# G888A.net
KiCad netlist of a schematic drawn in EAGLE
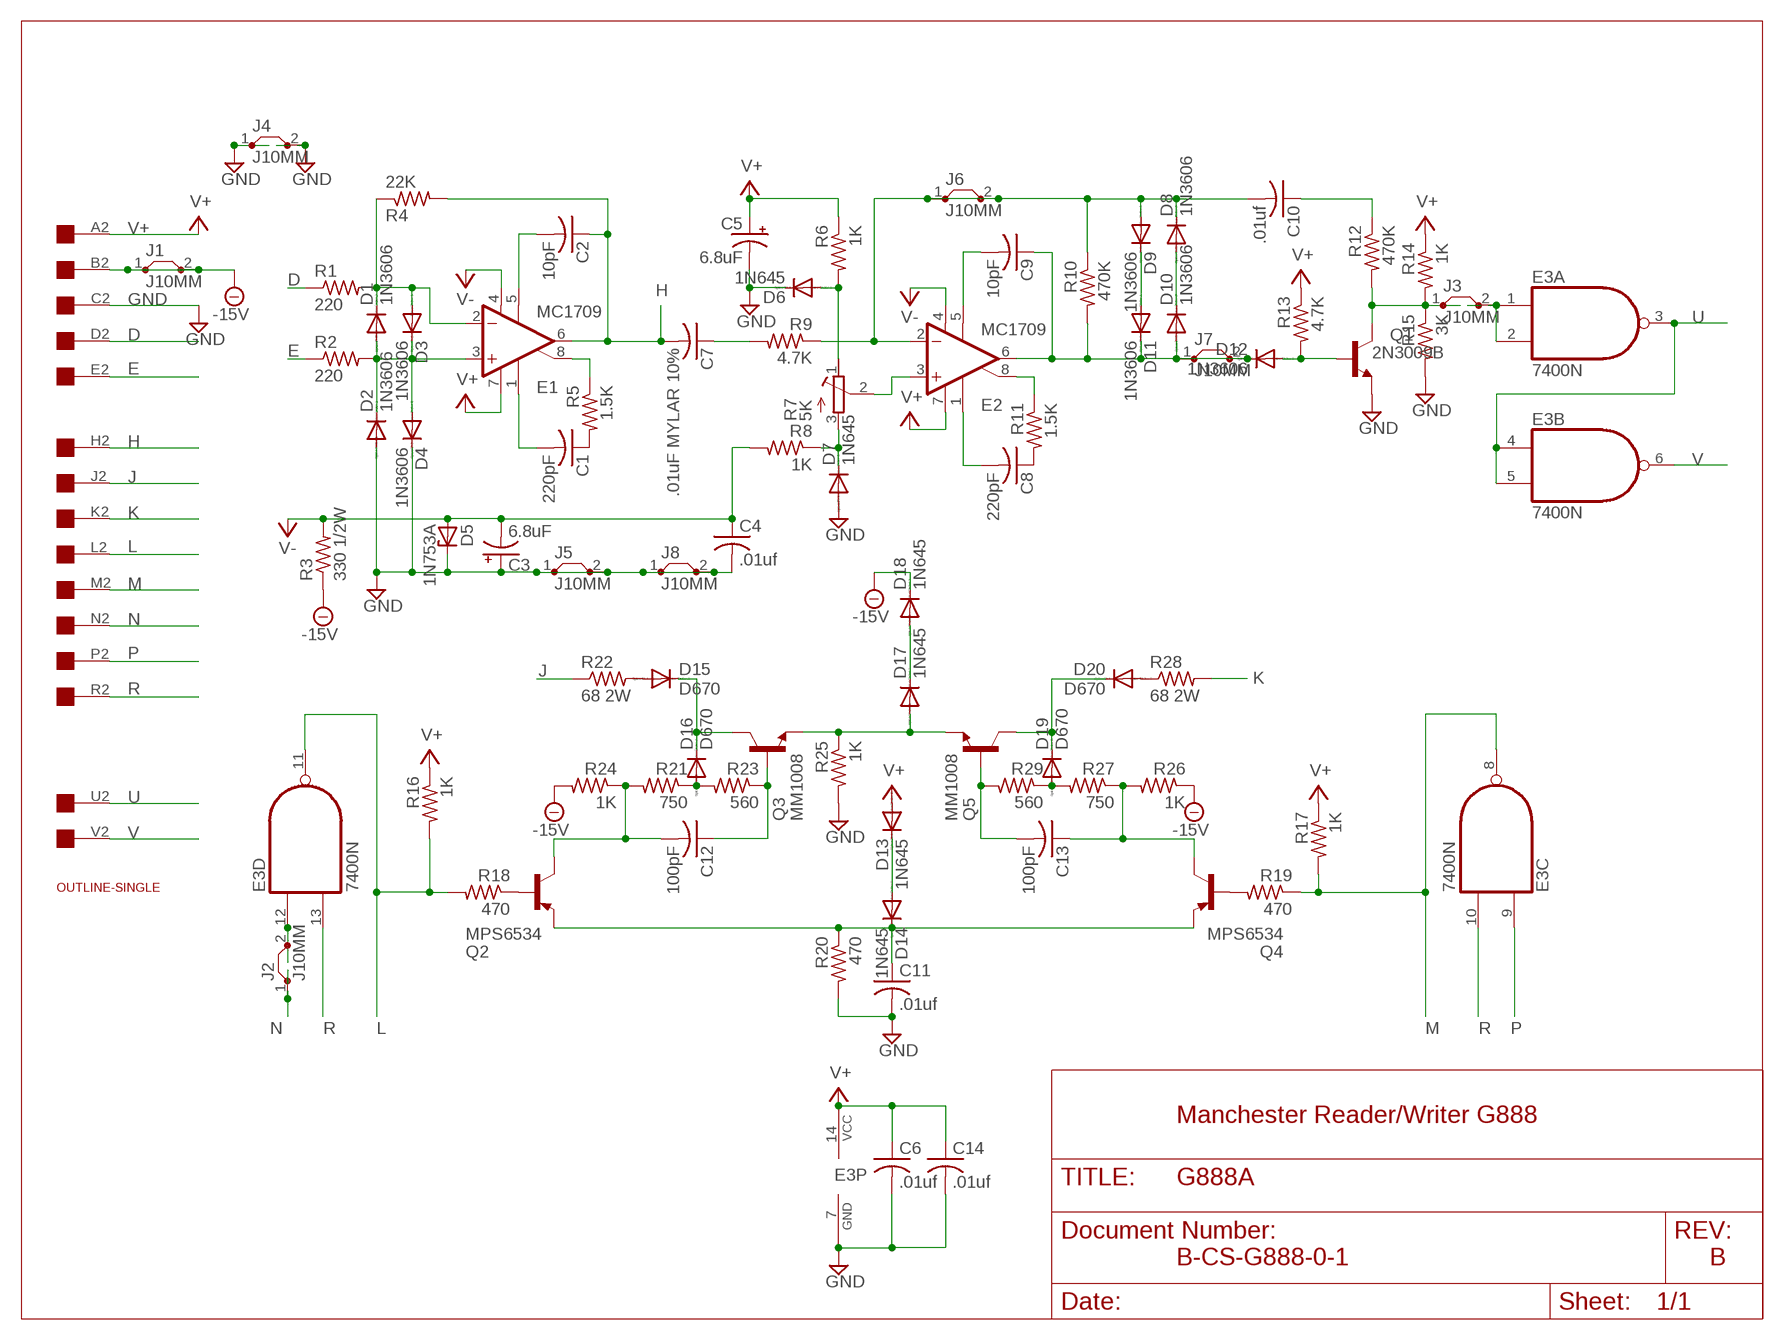
[diagram p0: schematic, sheet 1]

(export (version "E")
  (design (tool "Eeschema 10.0.6"))
  (components
    (comp (ref "C1")
      (value "220pF")
      (footprint "eagle-import:C050-025X075")
      (libsource (lib "eagle-import") (part "C-US050-025X075"))
    )
    (comp (ref "C2")
      (value "10pF")
      (footprint "eagle-import:C050-025X075")
      (libsource (lib "eagle-import") (part "C-US050-025X075"))
    )
    (comp (ref "C3")
      (value "6.8uF")
      (footprint "eagle-import:E12-8")
      (libsource (lib "eagle-import") (part "CPOL-USE20-8AXIAL"))
    )
    (comp (ref "C4")
      (value ".01uf")
      (footprint "eagle-import:C050-025X075")
      (libsource (lib "eagle-import") (part "C-US050-025X075"))
    )
    (comp (ref "C5")
      (value "6.8uF")
      (footprint "eagle-import:E12-8")
      (libsource (lib "eagle-import") (part "CPOL-USE20-8AXIAL"))
    )
    (comp (ref "C6")
      (value ".01uf")
      (footprint "eagle-import:C050-025X075")
      (libsource (lib "eagle-import") (part "C-US050-025X075"))
    )
    (comp (ref "C7")
      (value ".01uF MYLAR 10%")
      (footprint "eagle-import:C225-062X268")
      (libsource (lib "eagle-import") (part "C-US225-062X268"))
    )
    (comp (ref "C8")
      (value "220pF")
      (footprint "eagle-import:C050-025X075")
      (libsource (lib "eagle-import") (part "C-US050-025X075"))
    )
    (comp (ref "C9")
      (value "10pF")
      (footprint "eagle-import:C050-025X075")
      (libsource (lib "eagle-import") (part "C-US050-025X075"))
    )
    (comp (ref "C10")
      (value ".01uf")
      (footprint "eagle-import:C050-025X075")
      (libsource (lib "eagle-import") (part "C-US050-025X075"))
    )
    (comp (ref "C11")
      (value ".01uf")
      (footprint "eagle-import:C050-025X075")
      (libsource (lib "eagle-import") (part "C-US050-025X075"))
    )
    (comp (ref "C12")
      (value "100pF")
      (footprint "eagle-import:C050-025X075")
      (libsource (lib "eagle-import") (part "C-US050-025X075"))
    )
    (comp (ref "C13")
      (value "100pF")
      (footprint "eagle-import:C050-025X075")
      (libsource (lib "eagle-import") (part "C-US050-025X075"))
    )
    (comp (ref "C14")
      (value ".01uf")
      (footprint "eagle-import:C050-025X075")
      (libsource (lib "eagle-import") (part "C-US050-025X075"))
    )
    (comp (ref "D1")
      (value "1N3606")
      (footprint "eagle-import:DO35-10")
      (libsource (lib "eagle-import") (part "DIODE-DO35-10"))
    )
    (comp (ref "D2")
      (value "1N3606")
      (footprint "eagle-import:DO35-10")
      (libsource (lib "eagle-import") (part "DIODE-DO35-10"))
    )
    (comp (ref "D3")
      (value "1N3606")
      (footprint "eagle-import:DO35-10")
      (libsource (lib "eagle-import") (part "DIODE-DO35-10"))
    )
    (comp (ref "D4")
      (value "1N3606")
      (footprint "eagle-import:DO35-10")
      (libsource (lib "eagle-import") (part "DIODE-DO35-10"))
    )
    (comp (ref "D5")
      (value "1N753A")
      (footprint "eagle-import:DO35Z10")
      (libsource (lib "eagle-import") (part "ZENER-DIODEDO35Z10"))
    )
    (comp (ref "D6")
      (value "1N645")
      (footprint "eagle-import:DO35-10")
      (libsource (lib "eagle-import") (part "DIODE-DO35-10"))
    )
    (comp (ref "D7")
      (value "1N645")
      (footprint "eagle-import:DO35-10")
      (libsource (lib "eagle-import") (part "DIODE-DO35-10"))
    )
    (comp (ref "D8")
      (value "1N3606")
      (footprint "eagle-import:DO35-10")
      (libsource (lib "eagle-import") (part "DIODE-DO35-10"))
    )
    (comp (ref "D9")
      (value "1N3606")
      (footprint "eagle-import:DO35-10")
      (libsource (lib "eagle-import") (part "DIODE-DO35-10"))
    )
    (comp (ref "D10")
      (value "1N3606")
      (footprint "eagle-import:DO35-10")
      (libsource (lib "eagle-import") (part "DIODE-DO35-10"))
    )
    (comp (ref "D11")
      (value "1N3606")
      (footprint "eagle-import:DO35-10")
      (libsource (lib "eagle-import") (part "DIODE-DO35-10"))
    )
    (comp (ref "D12")
      (value "1N3606")
      (footprint "eagle-import:DO35-10")
      (libsource (lib "eagle-import") (part "DIODE-DO35-10"))
    )
    (comp (ref "D13")
      (value "1N645")
      (footprint "eagle-import:DO35-10")
      (libsource (lib "eagle-import") (part "DIODE-DO35-10"))
    )
    (comp (ref "D14")
      (value "1N645")
      (footprint "eagle-import:DO35-10")
      (libsource (lib "eagle-import") (part "DIODE-DO35-10"))
    )
    (comp (ref "D15")
      (value "D670")
      (footprint "eagle-import:DO35-10")
      (libsource (lib "eagle-import") (part "DIODE-DO35-10"))
    )
    (comp (ref "D16")
      (value "D670")
      (footprint "eagle-import:DO35-10")
      (libsource (lib "eagle-import") (part "DIODE-DO35-10"))
    )
    (comp (ref "D17")
      (value "1N645")
      (footprint "eagle-import:DO35-10")
      (libsource (lib "eagle-import") (part "DIODE-DO35-10"))
    )
    (comp (ref "D18")
      (value "1N645")
      (footprint "eagle-import:DO35-10")
      (libsource (lib "eagle-import") (part "DIODE-DO35-10"))
    )
    (comp (ref "D19")
      (value "D670")
      (footprint "eagle-import:DO35-10")
      (libsource (lib "eagle-import") (part "DIODE-DO35-10"))
    )
    (comp (ref "D20")
      (value "D670")
      (footprint "eagle-import:DO35-10")
      (libsource (lib "eagle-import") (part "DIODE-DO35-10"))
    )
    (comp (ref "E1")
      (value "MC1709")
      (footprint "eagle-import:H08C")
      (libsource (lib "eagle-import") (part "MC1709"))
    )
    (comp (ref "E2")
      (value "MC1709")
      (footprint "eagle-import:H08C")
      (libsource (lib "eagle-import") (part "MC1709"))
    )
    (comp (ref "E3")
      (value "7400N")
      (footprint "eagle-import:DIL14")
      (libsource (lib "eagle-import") (part "7400N"))
    )
    (comp (ref "J1")
      (value "J10MM")
      (footprint "eagle-import:10")
      (libsource (lib "eagle-import") (part "J10MM"))
    )
    (comp (ref "J2")
      (value "J10MM")
      (footprint "eagle-import:10")
      (libsource (lib "eagle-import") (part "J10MM"))
    )
    (comp (ref "J3")
      (value "J10MM")
      (footprint "eagle-import:10")
      (libsource (lib "eagle-import") (part "J10MM"))
    )
    (comp (ref "J4")
      (value "J10MM")
      (footprint "eagle-import:10")
      (libsource (lib "eagle-import") (part "J10MM"))
    )
    (comp (ref "J5")
      (value "J10MM")
      (footprint "eagle-import:10")
      (libsource (lib "eagle-import") (part "J10MM"))
    )
    (comp (ref "J6")
      (value "J10MM")
      (footprint "eagle-import:10")
      (libsource (lib "eagle-import") (part "J10MM"))
    )
    (comp (ref "J7")
      (value "J10MM")
      (footprint "eagle-import:10")
      (libsource (lib "eagle-import") (part "J10MM"))
    )
    (comp (ref "J8")
      (value "J10MM")
      (footprint "eagle-import:10")
      (libsource (lib "eagle-import") (part "J10MM"))
    )
    (comp (ref "Q1")
      (value "2N3009B")
      (footprint "eagle-import:TO39")
      (libsource (lib "eagle-import") (part "2N1711"))
    )
    (comp (ref "Q2")
      (value "MPS6534")
      (footprint "eagle-import:TO39")
      (libsource (lib "eagle-import") (part "2N5415"))
    )
    (comp (ref "Q3")
      (value "MM1008")
      (footprint "eagle-import:TO39")
      (libsource (lib "eagle-import") (part "2N1711"))
    )
    (comp (ref "Q4")
      (value "MPS6534")
      (footprint "eagle-import:TO39")
      (libsource (lib "eagle-import") (part "2N5415"))
    )
    (comp (ref "Q5")
      (value "MM1008")
      (footprint "eagle-import:TO39")
      (libsource (lib "eagle-import") (part "2N1711"))
    )
    (comp (ref "R1")
      (value "220")
      (footprint "eagle-import:0207_10")
      (libsource (lib "eagle-import") (part "R-US_0207/10"))
    )
    (comp (ref "R2")
      (value "220")
      (footprint "eagle-import:0207_10")
      (libsource (lib "eagle-import") (part "R-US_0207/10"))
    )
    (comp (ref "R3")
      (value "330 1/2W")
      (footprint "eagle-import:0411_15")
      (libsource (lib "eagle-import") (part "R-US_0411/15"))
    )
    (comp (ref "R4")
      (value "22K")
      (footprint "eagle-import:0207_10")
      (libsource (lib "eagle-import") (part "R-US_0207/10"))
    )
    (comp (ref "R5")
      (value "1.5K")
      (footprint "eagle-import:0207_10")
      (libsource (lib "eagle-import") (part "R-US_0207/10"))
    )
    (comp (ref "R6")
      (value "1K")
      (footprint "eagle-import:0207_10")
      (libsource (lib "eagle-import") (part "R-US_0207/10"))
    )
    (comp (ref "R7")
      (value "5K")
      (footprint "eagle-import:3006Y")
      (libsource (lib "eagle-import") (part "275P"))
    )
    (comp (ref "R8")
      (value "1K")
      (footprint "eagle-import:0207_10")
      (libsource (lib "eagle-import") (part "R-US_0207/10"))
    )
    (comp (ref "R9")
      (value "4.7K")
      (footprint "eagle-import:0207_10")
      (libsource (lib "eagle-import") (part "R-US_0207/10"))
    )
    (comp (ref "R10")
      (value "470K")
      (footprint "eagle-import:0207_10")
      (libsource (lib "eagle-import") (part "R-US_0207/10"))
    )
    (comp (ref "R11")
      (value "1.5K")
      (footprint "eagle-import:0207_10")
      (libsource (lib "eagle-import") (part "R-US_0207/10"))
    )
    (comp (ref "R12")
      (value "470K")
      (footprint "eagle-import:0207_10")
      (libsource (lib "eagle-import") (part "R-US_0207/10"))
    )
    (comp (ref "R13")
      (value "4.7K")
      (footprint "eagle-import:0207_10")
      (libsource (lib "eagle-import") (part "R-US_0207/10"))
    )
    (comp (ref "R14")
      (value "1K")
      (footprint "eagle-import:0207_10")
      (libsource (lib "eagle-import") (part "R-US_0207/10"))
    )
    (comp (ref "R15")
      (value "3K")
      (footprint "eagle-import:0207_10")
      (libsource (lib "eagle-import") (part "R-US_0207/10"))
    )
    (comp (ref "R16")
      (value "1K")
      (footprint "eagle-import:0207_10")
      (libsource (lib "eagle-import") (part "R-US_0207/10"))
    )
    (comp (ref "R17")
      (value "1K")
      (footprint "eagle-import:0207_10")
      (libsource (lib "eagle-import") (part "R-US_0207/10"))
    )
    (comp (ref "R18")
      (value "470")
      (footprint "eagle-import:0207_10")
      (libsource (lib "eagle-import") (part "R-US_0207/10"))
    )
    (comp (ref "R19")
      (value "470")
      (footprint "eagle-import:0207_10")
      (libsource (lib "eagle-import") (part "R-US_0207/10"))
    )
    (comp (ref "R20")
      (value "470")
      (footprint "eagle-import:0207_10")
      (libsource (lib "eagle-import") (part "R-US_0207/10"))
    )
    (comp (ref "R21")
      (value "750")
      (footprint "eagle-import:0207_10")
      (libsource (lib "eagle-import") (part "R-US_0207/10"))
    )
    (comp (ref "R22")
      (value "68 2W")
      (footprint "eagle-import:P0817_22")
      (libsource (lib "eagle-import") (part "R-US_0817/22"))
    )
    (comp (ref "R23")
      (value "560")
      (footprint "eagle-import:0207_10")
      (libsource (lib "eagle-import") (part "R-US_0207/10"))
    )
    (comp (ref "R24")
      (value "1K")
      (footprint "eagle-import:0207_10")
      (libsource (lib "eagle-import") (part "R-US_0207/10"))
    )
    (comp (ref "R25")
      (value "1K")
      (footprint "eagle-import:0207_10")
      (libsource (lib "eagle-import") (part "R-US_0207/10"))
    )
    (comp (ref "R26")
      (value "1K")
      (footprint "eagle-import:0207_10")
      (libsource (lib "eagle-import") (part "R-US_0207/10"))
    )
    (comp (ref "R27")
      (value "750")
      (footprint "eagle-import:0207_10")
      (libsource (lib "eagle-import") (part "R-US_0207/10"))
    )
    (comp (ref "R28")
      (value "68 2W")
      (footprint "eagle-import:P0817_22")
      (libsource (lib "eagle-import") (part "R-US_0817/22"))
    )
    (comp (ref "R29")
      (value "560")
      (footprint "eagle-import:0207_10")
      (libsource (lib "eagle-import") (part "R-US_0207/10"))
    )
    (comp (ref "U$1")
      (value "EDGE-1")
      (footprint "eagle-import:EDGE-CON1")
      (libsource (lib "eagle-import") (part "EDGE-1"))
    )
    (comp (ref "U$4")
      (value "OUTLINE-SINGLE")
      (footprint "eagle-import:SINGLE")
      (libsource (lib "eagle-import") (part "OUTLINE-SINGLE"))
    )
  )
  (nets
    (net (code "1") (name "-15V") (class "Default")
      (node (ref "D18") (pin "C") (pinfunction "C_C") (pintype "passive"))
      (node (ref "J1") (pin "1") (pinfunction "1_1") (pintype "passive"))
      (node (ref "J1") (pin "2") (pinfunction "2_2") (pintype "passive"))
      (node (ref "R24") (pin "2") (pinfunction "2_2") (pintype "passive"))
      (node (ref "R26") (pin "1") (pinfunction "1_1") (pintype "passive"))
      (node (ref "R3") (pin "1") (pinfunction "1_1") (pintype "passive"))
      (node (ref "U$1") (pin "B2") (pinfunction "1_B2") (pintype "bidirectional"))
    )
    (net (code "2") (name "/D") (class "Default")
      (node (ref "R1") (pin "1") (pinfunction "1_1") (pintype "passive"))
      (node (ref "U$1") (pin "D2") (pinfunction "1_D2") (pintype "bidirectional"))
    )
    (net (code "3") (name "/E") (class "Default")
      (node (ref "R2") (pin "1") (pinfunction "1_1") (pintype "passive"))
      (node (ref "U$1") (pin "E2") (pinfunction "1_E2") (pintype "bidirectional"))
    )
    (net (code "4") (name "/H") (class "Default")
      (node (ref "C2") (pin "1") (pinfunction "1_1") (pintype "passive"))
      (node (ref "C7") (pin "2") (pinfunction "2_2") (pintype "passive"))
      (node (ref "E1") (pin "6") (pinfunction "OUT_6") (pintype "output"))
      (node (ref "R4") (pin "2") (pinfunction "2_2") (pintype "passive"))
      (node (ref "U$1") (pin "H2") (pinfunction "1_H2") (pintype "bidirectional"))
    )
    (net (code "5") (name "/J") (class "Default")
      (node (ref "R22") (pin "1") (pinfunction "1_1") (pintype "passive"))
      (node (ref "U$1") (pin "J2") (pinfunction "1_J2") (pintype "bidirectional"))
    )
    (net (code "6") (name "/K") (class "Default")
      (node (ref "R28") (pin "2") (pinfunction "2_2") (pintype "passive"))
      (node (ref "U$1") (pin "K2") (pinfunction "1_K2") (pintype "bidirectional"))
    )
    (net (code "7") (name "/L") (class "Default")
      (node (ref "E3") (pin "11") (pinfunction "O_11") (pintype "output"))
      (node (ref "R16") (pin "2") (pinfunction "2_2") (pintype "passive"))
      (node (ref "R18") (pin "2") (pinfunction "2_2") (pintype "passive"))
      (node (ref "U$1") (pin "L2") (pinfunction "1_L2") (pintype "bidirectional"))
    )
    (net (code "8") (name "/M") (class "Default")
      (node (ref "E3") (pin "8") (pinfunction "O_8") (pintype "output"))
      (node (ref "R17") (pin "2") (pinfunction "2_2") (pintype "passive"))
      (node (ref "R19") (pin "1") (pinfunction "1_1") (pintype "passive"))
      (node (ref "U$1") (pin "M2") (pinfunction "1_M2") (pintype "bidirectional"))
    )
    (net (code "9") (name "/N") (class "Default")
      (node (ref "E3") (pin "12") (pinfunction "I0_12") (pintype "input"))
      (node (ref "J2") (pin "1") (pinfunction "1_1") (pintype "passive"))
      (node (ref "J2") (pin "2") (pinfunction "2_2") (pintype "passive"))
      (node (ref "U$1") (pin "N2") (pinfunction "1_N2") (pintype "bidirectional"))
    )
    (net (code "10") (name "/P") (class "Default")
      (node (ref "E3") (pin "9") (pinfunction "I0_9") (pintype "input"))
      (node (ref "U$1") (pin "P2") (pinfunction "1_P2") (pintype "bidirectional"))
    )
    (net (code "11") (name "/R") (class "Default")
      (node (ref "E3") (pin "10") (pinfunction "I1_10") (pintype "input"))
      (node (ref "E3") (pin "13") (pinfunction "I1_13") (pintype "input"))
      (node (ref "U$1") (pin "R2") (pinfunction "1_R2") (pintype "bidirectional"))
    )
    (net (code "12") (name "/U") (class "Default")
      (node (ref "E3") (pin "3") (pinfunction "O_3") (pintype "output"))
      (node (ref "E3") (pin "4") (pinfunction "I0_4") (pintype "input"))
      (node (ref "E3") (pin "5") (pinfunction "I1_5") (pintype "input"))
      (node (ref "U$1") (pin "U2") (pinfunction "1_U2") (pintype "bidirectional"))
    )
    (net (code "13") (name "/V") (class "Default")
      (node (ref "E3") (pin "6") (pinfunction "O_6") (pintype "output"))
      (node (ref "U$1") (pin "V2") (pinfunction "1_V2") (pintype "bidirectional"))
    )
    (net (code "14") (name "GND") (class "Default")
      (node (ref "C11") (pin "2") (pinfunction "2_2") (pintype "passive"))
      (node (ref "C14") (pin "2") (pinfunction "2_2") (pintype "passive"))
      (node (ref "C3") (pin "+") (pinfunction "+_+") (pintype "passive"))
      (node (ref "C4") (pin "2") (pinfunction "2_2") (pintype "passive"))
      (node (ref "C5") (pin "-") (pinfunction "-_-") (pintype "passive"))
      (node (ref "C6") (pin "2") (pinfunction "2_2") (pintype "passive"))
      (node (ref "D2") (pin "A") (pinfunction "A_A") (pintype "passive"))
      (node (ref "D4") (pin "C") (pinfunction "C_C") (pintype "passive"))
      (node (ref "D5") (pin "C") (pinfunction "C_C") (pintype "passive"))
      (node (ref "D6") (pin "C") (pinfunction "C_C") (pintype "passive"))
      (node (ref "D7") (pin "A") (pinfunction "A_A") (pintype "passive"))
      (node (ref "E3") (pin "7") (pinfunction "GND_7") (pintype "power_in"))
      (node (ref "J4") (pin "1") (pinfunction "1_1") (pintype "passive"))
      (node (ref "J4") (pin "2") (pinfunction "2_2") (pintype "passive"))
      (node (ref "J5") (pin "1") (pinfunction "1_1") (pintype "passive"))
      (node (ref "J5") (pin "2") (pinfunction "2_2") (pintype "passive"))
      (node (ref "J8") (pin "1") (pinfunction "1_1") (pintype "passive"))
      (node (ref "J8") (pin "2") (pinfunction "2_2") (pintype "passive"))
      (node (ref "Q1") (pin "1") (pinfunction "E_1") (pintype "passive"))
      (node (ref "R15") (pin "2") (pinfunction "2_2") (pintype "passive"))
      (node (ref "R20") (pin "2") (pinfunction "2_2") (pintype "passive"))
      (node (ref "R25") (pin "2") (pinfunction "2_2") (pintype "passive"))
      (node (ref "U$1") (pin "C2") (pinfunction "1_C2") (pintype "bidirectional"))
    )
    (net (code "15") (name "Net-(C1-Pad1)") (class "Default")
      (node (ref "C1") (pin "1") (pinfunction "1_1") (pintype "passive"))
      (node (ref "R5") (pin "2") (pinfunction "2_2") (pintype "passive"))
    )
    (net (code "16") (name "Net-(C7-Pad1)") (class "Default")
      (node (ref "C7") (pin "1") (pinfunction "1_1") (pintype "passive"))
      (node (ref "R9") (pin "2") (pinfunction "2_2") (pintype "passive"))
    )
    (net (code "17") (name "Net-(C8-Pad1)") (class "Default")
      (node (ref "C8") (pin "1") (pinfunction "1_1") (pintype "passive"))
      (node (ref "R11") (pin "2") (pinfunction "2_2") (pintype "passive"))
    )
    (net (code "18") (name "Net-(C10-Pad1)") (class "Default")
      (node (ref "C10") (pin "1") (pinfunction "1_1") (pintype "passive"))
      (node (ref "R12") (pin "1") (pinfunction "1_1") (pintype "passive"))
    )
    (net (code "19") (name "Net-(D10-PadC)") (class "Default")
      (node (ref "D10") (pin "C") (pinfunction "C_C") (pintype "passive"))
      (node (ref "D8") (pin "A") (pinfunction "A_A") (pintype "passive"))
    )
    (net (code "20") (name "Net-(D11-PadA)") (class "Default")
      (node (ref "D11") (pin "A") (pinfunction "A_A") (pintype "passive"))
      (node (ref "D9") (pin "C") (pinfunction "C_C") (pintype "passive"))
    )
    (net (code "21") (name "Net-(D13-PadC)") (class "Default")
      (node (ref "D13") (pin "C") (pinfunction "C_C") (pintype "passive"))
      (node (ref "D14") (pin "A") (pinfunction "A_A") (pintype "passive"))
    )
    (net (code "22") (name "Net-(D15-PadA)") (class "Default")
      (node (ref "D15") (pin "A") (pinfunction "A_A") (pintype "passive"))
      (node (ref "R22") (pin "2") (pinfunction "2_2") (pintype "passive"))
    )
    (net (code "23") (name "Net-(D16-PadA)") (class "Default")
      (node (ref "D16") (pin "A") (pinfunction "A_A") (pintype "passive"))
      (node (ref "R21") (pin "1") (pinfunction "1_1") (pintype "passive"))
      (node (ref "R23") (pin "2") (pinfunction "2_2") (pintype "passive"))
    )
    (net (code "24") (name "Net-(D17-PadC)") (class "Default")
      (node (ref "D17") (pin "C") (pinfunction "C_C") (pintype "passive"))
      (node (ref "D18") (pin "A") (pinfunction "A_A") (pintype "passive"))
    )
    (net (code "25") (name "Net-(D19-PadA)") (class "Default")
      (node (ref "D19") (pin "A") (pinfunction "A_A") (pintype "passive"))
      (node (ref "R27") (pin "2") (pinfunction "2_2") (pintype "passive"))
      (node (ref "R29") (pin "1") (pinfunction "1_1") (pintype "passive"))
    )
    (net (code "26") (name "Net-(D20-PadA)") (class "Default")
      (node (ref "D20") (pin "A") (pinfunction "A_A") (pintype "passive"))
      (node (ref "R28") (pin "1") (pinfunction "1_1") (pintype "passive"))
    )
    (net (code "27") (name "Net-(E1-+IN)") (class "Default")
      (node (ref "D1") (pin "A") (pinfunction "A_A") (pintype "passive"))
      (node (ref "D2") (pin "C") (pinfunction "C_C") (pintype "passive"))
      (node (ref "D3") (pin "C") (pinfunction "C_C") (pintype "passive"))
      (node (ref "D4") (pin "A") (pinfunction "A_A") (pintype "passive"))
      (node (ref "E1") (pin "3") (pinfunction "+IN_3") (pintype "input"))
      (node (ref "R2") (pin "2") (pinfunction "2_2") (pintype "passive"))
    )
    (net (code "28") (name "Net-(E1--IN)") (class "Default")
      (node (ref "D1") (pin "C") (pinfunction "C_C") (pintype "passive"))
      (node (ref "D3") (pin "A") (pinfunction "A_A") (pintype "passive"))
      (node (ref "E1") (pin "2") (pinfunction "-IN_2") (pintype "input"))
      (node (ref "R1") (pin "2") (pinfunction "2_2") (pintype "passive"))
      (node (ref "R4") (pin "1") (pinfunction "1_1") (pintype "passive"))
    )
    (net (code "29") (name "Net-(E1-ON1)") (class "Default")
      (node (ref "C1") (pin "2") (pinfunction "2_2") (pintype "passive"))
      (node (ref "E1") (pin "1") (pinfunction "ON1_1") (pintype "passive"))
    )
    (net (code "30") (name "Net-(E1-ON2)") (class "Default")
      (node (ref "E1") (pin "8") (pinfunction "ON2_8") (pintype "passive"))
      (node (ref "R5") (pin "1") (pinfunction "1_1") (pintype "passive"))
    )
    (net (code "31") (name "Net-(E1-OPT)") (class "Default")
      (node (ref "C2") (pin "2") (pinfunction "2_2") (pintype "passive"))
      (node (ref "E1") (pin "5") (pinfunction "OPT_5") (pintype "passive"))
    )
    (net (code "32") (name "Net-(E2-+IN)") (class "Default")
      (node (ref "E2") (pin "3") (pinfunction "+IN_3") (pintype "input"))
      (node (ref "R7") (pin "2") (pinfunction "S_2") (pintype "passive"))
    )
    (net (code "33") (name "Net-(E2--IN)") (class "Default")
      (node (ref "C10") (pin "2") (pinfunction "2_2") (pintype "passive"))
      (node (ref "D8") (pin "C") (pinfunction "C_C") (pintype "passive"))
      (node (ref "D9") (pin "A") (pinfunction "A_A") (pintype "passive"))
      (node (ref "E2") (pin "2") (pinfunction "-IN_2") (pintype "input"))
      (node (ref "J6") (pin "1") (pinfunction "1_1") (pintype "passive"))
      (node (ref "J6") (pin "2") (pinfunction "2_2") (pintype "passive"))
      (node (ref "R10") (pin "1") (pinfunction "1_1") (pintype "passive"))
      (node (ref "R9") (pin "1") (pinfunction "1_1") (pintype "passive"))
    )
    (net (code "34") (name "Net-(E2-ON1)") (class "Default")
      (node (ref "C8") (pin "2") (pinfunction "2_2") (pintype "passive"))
      (node (ref "E2") (pin "1") (pinfunction "ON1_1") (pintype "passive"))
    )
    (net (code "35") (name "Net-(E2-ON2)") (class "Default")
      (node (ref "E2") (pin "8") (pinfunction "ON2_8") (pintype "passive"))
      (node (ref "R11") (pin "1") (pinfunction "1_1") (pintype "passive"))
    )
    (net (code "36") (name "Net-(E2-OPT)") (class "Default")
      (node (ref "C9") (pin "2") (pinfunction "2_2") (pintype "passive"))
      (node (ref "E2") (pin "5") (pinfunction "OPT_5") (pintype "passive"))
    )
    (net (code "37") (name "Net-(E2-OUT)") (class "Default")
      (node (ref "C9") (pin "1") (pinfunction "1_1") (pintype "passive"))
      (node (ref "D10") (pin "A") (pinfunction "A_A") (pintype "passive"))
      (node (ref "D11") (pin "C") (pinfunction "C_C") (pintype "passive"))
      (node (ref "D12") (pin "C") (pinfunction "C_C") (pintype "passive"))
      (node (ref "E2") (pin "6") (pinfunction "OUT_6") (pintype "output"))
      (node (ref "J7") (pin "1") (pinfunction "1_1") (pintype "passive"))
      (node (ref "J7") (pin "2") (pinfunction "2_2") (pintype "passive"))
      (node (ref "R10") (pin "2") (pinfunction "2_2") (pintype "passive"))
    )
    (net (code "38") (name "Net-(E3A-I0)") (class "Default")
      (node (ref "E3") (pin "1") (pinfunction "I0_1") (pintype "input"))
      (node (ref "E3") (pin "2") (pinfunction "I1_2") (pintype "input"))
      (node (ref "J3") (pin "1") (pinfunction "1_1") (pintype "passive"))
      (node (ref "J3") (pin "2") (pinfunction "2_2") (pintype "passive"))
      (node (ref "Q1") (pin "3") (pinfunction "C_3") (pintype "passive"))
      (node (ref "R12") (pin "2") (pinfunction "2_2") (pintype "passive"))
      (node (ref "R14") (pin "2") (pinfunction "2_2") (pintype "passive"))
      (node (ref "R15") (pin "1") (pinfunction "1_1") (pintype "passive"))
    )
    (net (code "39") (name "Net-(Q1-B)") (class "Default")
      (node (ref "D12") (pin "A") (pinfunction "A_A") (pintype "passive"))
      (node (ref "Q1") (pin "2") (pinfunction "B_2") (pintype "passive"))
      (node (ref "R13") (pin "2") (pinfunction "2_2") (pintype "passive"))
    )
    (net (code "40") (name "Net-(Q2-B)") (class "Default")
      (node (ref "Q2") (pin "2") (pinfunction "B_2") (pintype "passive"))
      (node (ref "R18") (pin "1") (pinfunction "1_1") (pintype "passive"))
    )
    (net (code "41") (name "Net-(Q2-C)") (class "Default")
      (node (ref "C12") (pin "2") (pinfunction "2_2") (pintype "passive"))
      (node (ref "Q2") (pin "3") (pinfunction "C_3") (pintype "passive"))
      (node (ref "R21") (pin "2") (pinfunction "2_2") (pintype "passive"))
      (node (ref "R24") (pin "1") (pinfunction "1_1") (pintype "passive"))
    )
    (net (code "42") (name "Net-(Q2-E)") (class "Default")
      (node (ref "C11") (pin "1") (pinfunction "1_1") (pintype "passive"))
      (node (ref "D14") (pin "C") (pinfunction "C_C") (pintype "passive"))
      (node (ref "Q2") (pin "1") (pinfunction "E_1") (pintype "passive"))
      (node (ref "Q4") (pin "1") (pinfunction "E_1") (pintype "passive"))
      (node (ref "R20") (pin "1") (pinfunction "1_1") (pintype "passive"))
    )
    (net (code "43") (name "Net-(Q3-B)") (class "Default")
      (node (ref "C12") (pin "1") (pinfunction "1_1") (pintype "passive"))
      (node (ref "Q3") (pin "2") (pinfunction "B_2") (pintype "passive"))
      (node (ref "R23") (pin "1") (pinfunction "1_1") (pintype "passive"))
    )
    (net (code "44") (name "Net-(Q3-C)") (class "Default")
      (node (ref "D15") (pin "C") (pinfunction "C_C") (pintype "passive"))
      (node (ref "D16") (pin "C") (pinfunction "C_C") (pintype "passive"))
      (node (ref "Q3") (pin "3") (pinfunction "C_3") (pintype "passive"))
    )
    (net (code "45") (name "Net-(Q3-E)") (class "Default")
      (node (ref "D17") (pin "A") (pinfunction "A_A") (pintype "passive"))
      (node (ref "Q3") (pin "1") (pinfunction "E_1") (pintype "passive"))
      (node (ref "Q5") (pin "1") (pinfunction "E_1") (pintype "passive"))
      (node (ref "R25") (pin "1") (pinfunction "1_1") (pintype "passive"))
    )
    (net (code "46") (name "Net-(Q4-B)") (class "Default")
      (node (ref "Q4") (pin "2") (pinfunction "B_2") (pintype "passive"))
      (node (ref "R19") (pin "2") (pinfunction "2_2") (pintype "passive"))
    )
    (net (code "47") (name "Net-(Q4-C)") (class "Default")
      (node (ref "C13") (pin "1") (pinfunction "1_1") (pintype "passive"))
      (node (ref "Q4") (pin "3") (pinfunction "C_3") (pintype "passive"))
      (node (ref "R26") (pin "2") (pinfunction "2_2") (pintype "passive"))
      (node (ref "R27") (pin "1") (pinfunction "1_1") (pintype "passive"))
    )
    (net (code "48") (name "Net-(Q5-B)") (class "Default")
      (node (ref "C13") (pin "2") (pinfunction "2_2") (pintype "passive"))
      (node (ref "Q5") (pin "2") (pinfunction "B_2") (pintype "passive"))
      (node (ref "R29") (pin "2") (pinfunction "2_2") (pintype "passive"))
    )
    (net (code "49") (name "Net-(Q5-C)") (class "Default")
      (node (ref "D19") (pin "C") (pinfunction "C_C") (pintype "passive"))
      (node (ref "D20") (pin "C") (pinfunction "C_C") (pintype "passive"))
      (node (ref "Q5") (pin "3") (pinfunction "C_3") (pintype "passive"))
    )
    (net (code "50") (name "Net-(R7-A)") (class "Default")
      (node (ref "D6") (pin "A") (pinfunction "A_A") (pintype "passive"))
      (node (ref "R6") (pin "2") (pinfunction "2_2") (pintype "passive"))
      (node (ref "R7") (pin "1") (pinfunction "A_1") (pintype "passive"))
    )
    (net (code "51") (name "Net-(R7-E)") (class "Default")
      (node (ref "D7") (pin "C") (pinfunction "C_C") (pintype "passive"))
      (node (ref "R7") (pin "3") (pinfunction "E_3") (pintype "passive"))
      (node (ref "R8") (pin "1") (pinfunction "1_1") (pintype "passive"))
    )
    (net (code "52") (name "V+") (class "Default")
      (node (ref "C14") (pin "1") (pinfunction "1_1") (pintype "passive"))
      (node (ref "C5") (pin "+") (pinfunction "+_+") (pintype "passive"))
      (node (ref "C6") (pin "1") (pinfunction "1_1") (pintype "passive"))
      (node (ref "D13") (pin "A") (pinfunction "A_A") (pintype "passive"))
      (node (ref "E1") (pin "7") (pinfunction "V+_7") (pintype "power_in"))
      (node (ref "E2") (pin "7") (pinfunction "V+_7") (pintype "power_in"))
      (node (ref "E3") (pin "14") (pinfunction "VCC_14") (pintype "power_in"))
      (node (ref "R13") (pin "1") (pinfunction "1_1") (pintype "passive"))
      (node (ref "R14") (pin "1") (pinfunction "1_1") (pintype "passive"))
      (node (ref "R16") (pin "1") (pinfunction "1_1") (pintype "passive"))
      (node (ref "R17") (pin "1") (pinfunction "1_1") (pintype "passive"))
      (node (ref "R6") (pin "1") (pinfunction "1_1") (pintype "passive"))
      (node (ref "U$1") (pin "A2") (pinfunction "1_A2") (pintype "bidirectional"))
    )
    (net (code "53") (name "V-") (class "Default")
      (node (ref "C3") (pin "-") (pinfunction "-_-") (pintype "passive"))
      (node (ref "C4") (pin "1") (pinfunction "1_1") (pintype "passive"))
      (node (ref "D5") (pin "A") (pinfunction "A_A") (pintype "passive"))
      (node (ref "E1") (pin "4") (pinfunction "V-_4") (pintype "power_in"))
      (node (ref "E2") (pin "4") (pinfunction "V-_4") (pintype "power_in"))
      (node (ref "R3") (pin "2") (pinfunction "2_2") (pintype "passive"))
      (node (ref "R8") (pin "2") (pinfunction "2_2") (pintype "passive"))
    )
  )
)
